# connect.net
KiCad netlist of a schematic drawn in Altium Designer
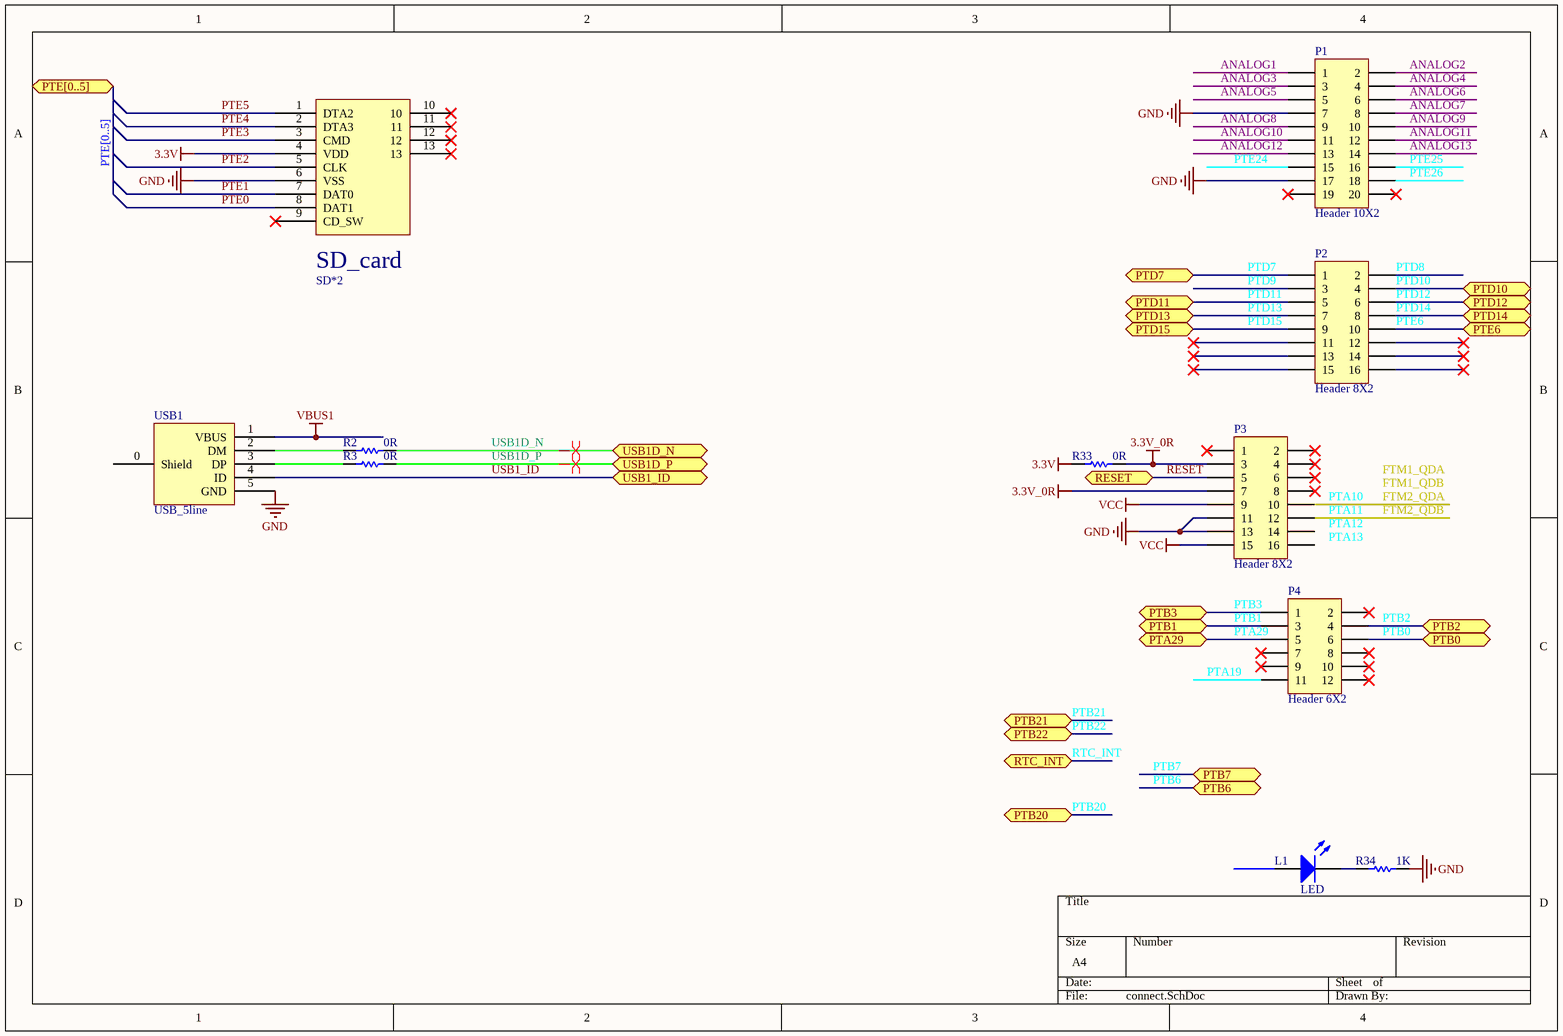
[diagram p0: connect.SchDoc]

(export (version "E")
  (design (tool "Eeschema 10.0.6"))
  (components
    (comp (ref "L1") (value "LED") (footprint "1608[0603]") (libsource (lib "Sparks") (part "LED")))
    (comp (ref "P1")
      (value "Header 10X2")
      (footprint "HDR2X10")
      (description "Header, 10-Pin, Dual row")
      (fields (field (name "PUBLISHER") "Altium Limited"))
      (libsource (lib "Sparks") (part "Header 10X2"))
    )
    (comp (ref "P2")
      (value "Header 8X2")
      (footprint "HDR2X8")
      (description "Header, 8-Pin, Dual row")
      (fields (field (name "PUBLISHER") "Altium Limited"))
      (libsource (lib "Sparks") (part "Header 8X2"))
    )
    (comp (ref "P3")
      (value "Header 8X2")
      (footprint "HDR2X8")
      (description "Header, 8-Pin, Dual row")
      (fields (field (name "PUBLISHER") "Altium Limited"))
      (libsource (lib "Sparks") (part "Header 8X2"))
    )
    (comp (ref "P4")
      (value "Header 6X2")
      (footprint "HDR2X6")
      (description "Header, 6-Pin, Dual row")
      (fields (field (name "PUBLISHER") "Altium Limited"))
      (libsource (lib "Sparks") (part "Header 6X2"))
    )
    (comp (ref "R2")
      (value "0R")
      (footprint "1608[0603]")
      (description "贴片电阻")
      (fields (field (name "Comment") "Res") (field (name "PUBLISHER") "Altium Limited"))
      (libsource (lib "Sparks") (part "Res"))
    )
    (comp (ref "R3")
      (value "0R")
      (footprint "1608[0603]")
      (description "贴片电阻")
      (fields (field (name "Comment") "Res") (field (name "PUBLISHER") "Altium Limited"))
      (libsource (lib "Sparks") (part "Res"))
    )
    (comp (ref "R33")
      (value "0R")
      (footprint "1206")
      (description "贴片电阻")
      (fields (field (name "Comment") "Res") (field (name "PUBLISHER") "Altium Limited"))
      (libsource (lib "Sparks") (part "Res"))
    )
    (comp (ref "R34")
      (value "1K")
      (footprint "1608[0603]")
      (description "贴片电阻")
      (fields (field (name "Comment") "Res") (field (name "PUBLISHER") "Altium Limited"))
      (libsource (lib "Sparks") (part "Res"))
    )
    (comp (ref "SD*2") (value "TF_card") (footprint "TF卡座(短体)") (libsource (lib "2号库") (part "TF_card")))
    (comp (ref "USB1")
      (value "USB_5line")
      (footprint "USB-MICRO-5P-2F")
      (libsource (lib "2号库") (part "USB_5line"))
    )
  )
  (nets
    (net (code "1") (name "/ANALOG1") (class "Default")
      (node (ref "P1") (pin "1") (pinfunction "1_1") (pintype "passive"))
    )
    (net (code "2") (name "/ANALOG2") (class "Default")
      (node (ref "P1") (pin "2") (pinfunction "2_2") (pintype "passive"))
    )
    (net (code "3") (name "/ANALOG3") (class "Default")
      (node (ref "P1") (pin "3") (pinfunction "3_3") (pintype "passive"))
    )
    (net (code "4") (name "/ANALOG4") (class "Default")
      (node (ref "P1") (pin "4") (pinfunction "4_4") (pintype "passive"))
    )
    (net (code "5") (name "/ANALOG5") (class "Default")
      (node (ref "P1") (pin "5") (pinfunction "5_5") (pintype "passive"))
    )
    (net (code "6") (name "/ANALOG6") (class "Default")
      (node (ref "P1") (pin "6") (pinfunction "6_6") (pintype "passive"))
    )
    (net (code "7") (name "/ANALOG7") (class "Default")
      (node (ref "P1") (pin "8") (pinfunction "8_8") (pintype "passive"))
    )
    (net (code "8") (name "/ANALOG8") (class "Default")
      (node (ref "P1") (pin "9") (pinfunction "9_9") (pintype "passive"))
    )
    (net (code "9") (name "/ANALOG9") (class "Default")
      (node (ref "P1") (pin "10") (pinfunction "10_10") (pintype "passive"))
    )
    (net (code "10") (name "/ANALOG10") (class "Default")
      (node (ref "P1") (pin "11") (pinfunction "11_11") (pintype "passive"))
    )
    (net (code "11") (name "/ANALOG11") (class "Default")
      (node (ref "P1") (pin "12") (pinfunction "12_12") (pintype "passive"))
    )
    (net (code "12") (name "/ANALOG12") (class "Default")
      (node (ref "P1") (pin "13") (pinfunction "13_13") (pintype "passive"))
    )
    (net (code "13") (name "/ANALOG13") (class "Default")
      (node (ref "P1") (pin "14") (pinfunction "14_14") (pintype "passive"))
    )
    (net (code "16") (name "/FTM2_QDA") (class "Default")
      (node (ref "P3") (pin "10") (pinfunction "10_10") (pintype "passive"))
    )
    (net (code "17") (name "/FTM2_QDB") (class "Default")
      (node (ref "P3") (pin "12") (pinfunction "12_12") (pintype "passive"))
    )
    (net (code "20") (name "/PTA19") (class "Default")
      (node (ref "P4") (pin "11") (pinfunction "11_11") (pintype "passive"))
    )
    (net (code "21") (name "/PTA29") (class "Default")
      (node (ref "P4") (pin "5") (pinfunction "5_5") (pintype "passive"))
    )
    (net (code "22") (name "/PTB0") (class "Default")
      (node (ref "P4") (pin "6") (pinfunction "6_6") (pintype "passive"))
    )
    (net (code "23") (name "/PTB1") (class "Default")
      (node (ref "P4") (pin "3") (pinfunction "3_3") (pintype "passive"))
    )
    (net (code "24") (name "/PTB2") (class "Default")
      (node (ref "P4") (pin "4") (pinfunction "4_4") (pintype "passive"))
    )
    (net (code "25") (name "/PTB3") (class "Default")
      (node (ref "P4") (pin "1") (pinfunction "1_1") (pintype "passive"))
    )
    (net (code "31") (name "/PTD7") (class "Default")
      (node (ref "P2") (pin "1") (pinfunction "1_1") (pintype "passive"))
    )
    (net (code "32") (name "/PTD8") (class "Default")
      (node (ref "P2") (pin "2") (pinfunction "2_2") (pintype "passive"))
    )
    (net (code "33") (name "/PTD9") (class "Default")
      (node (ref "P2") (pin "3") (pinfunction "3_3") (pintype "passive"))
    )
    (net (code "34") (name "/PTD10") (class "Default")
      (node (ref "P2") (pin "4") (pinfunction "4_4") (pintype "passive"))
    )
    (net (code "35") (name "/PTD11") (class "Default")
      (node (ref "P2") (pin "5") (pinfunction "5_5") (pintype "passive"))
    )
    (net (code "36") (name "/PTD12") (class "Default")
      (node (ref "P2") (pin "6") (pinfunction "6_6") (pintype "passive"))
    )
    (net (code "37") (name "/PTD13") (class "Default")
      (node (ref "P2") (pin "7") (pinfunction "7_7") (pintype "passive"))
    )
    (net (code "38") (name "/PTD14") (class "Default")
      (node (ref "P2") (pin "8") (pinfunction "8_8") (pintype "passive"))
    )
    (net (code "39") (name "/PTD15") (class "Default")
      (node (ref "P2") (pin "9") (pinfunction "9_9") (pintype "passive"))
    )
    (net (code "40") (name "/PTE0") (class "Default")
      (node (ref "SD*2") (pin "8") (pinfunction "DAT1_8") (pintype "passive"))
    )
    (net (code "41") (name "/PTE1") (class "Default")
      (node (ref "SD*2") (pin "7") (pinfunction "DAT0_7") (pintype "passive"))
    )
    (net (code "42") (name "/PTE2") (class "Default")
      (node (ref "SD*2") (pin "5") (pinfunction "CLK_5") (pintype "passive"))
    )
    (net (code "43") (name "/PTE3") (class "Default")
      (node (ref "SD*2") (pin "3") (pinfunction "CMD_3") (pintype "passive"))
    )
    (net (code "44") (name "/PTE4") (class "Default")
      (node (ref "SD*2") (pin "2") (pinfunction "DTA3_2") (pintype "passive"))
    )
    (net (code "45") (name "/PTE5") (class "Default")
      (node (ref "SD*2") (pin "1") (pinfunction "DTA2_1") (pintype "passive"))
    )
    (net (code "46") (name "/PTE6") (class "Default")
      (node (ref "P2") (pin "10") (pinfunction "10_10") (pintype "passive"))
    )
    (net (code "47") (name "/PTE24") (class "Default")
      (node (ref "P1") (pin "15") (pinfunction "15_15") (pintype "passive"))
    )
    (net (code "48") (name "/PTE25") (class "Default")
      (node (ref "P1") (pin "16") (pinfunction "16_16") (pintype "passive"))
    )
    (net (code "49") (name "/PTE26") (class "Default")
      (node (ref "P1") (pin "18") (pinfunction "18_18") (pintype "passive"))
    )
    (net (code "51") (name "/RESET") (class "Default")
      (node (ref "P3") (pin "5") (pinfunction "5_5") (pintype "passive"))
    )
    (net (code "53") (name "/USB1D_N") (class "Default")
      (node (ref "R2") (pin "1") (pinfunction "1_1") (pintype "passive"))
    )
    (net (code "54") (name "/USB1D_P") (class "Default")
      (node (ref "R3") (pin "1") (pinfunction "1_1") (pintype "passive"))
    )
    (net (code "55") (name "/USB1_ID") (class "Default")
      (node (ref "USB1") (pin "4") (pinfunction "ID_4") (pintype "passive"))
    )
    (net (code "56") (name "3.3V") (class "Default")
      (node (ref "R33") (pin "2") (pinfunction "2_2") (pintype "passive"))
      (node (ref "SD*2") (pin "4") (pinfunction "VDD_4") (pintype "passive"))
    )
    (net (code "57") (name "3.3V_0R") (class "Default")
      (node (ref "P3") (pin "3") (pinfunction "3_3") (pintype "passive"))
      (node (ref "P3") (pin "7") (pinfunction "7_7") (pintype "passive"))
      (node (ref "R33") (pin "1") (pinfunction "1_1") (pintype "passive"))
    )
    (net (code "58") (name "GND") (class "Default")
      (node (ref "P1") (pin "17") (pinfunction "17_17") (pintype "passive"))
      (node (ref "P1") (pin "7") (pinfunction "7_7") (pintype "passive"))
      (node (ref "P3") (pin "11") (pinfunction "11_11") (pintype "passive"))
      (node (ref "P3") (pin "13") (pinfunction "13_13") (pintype "passive"))
      (node (ref "R34") (pin "1") (pinfunction "1_1") (pintype "passive"))
      (node (ref "SD*2") (pin "6") (pinfunction "VSS_6") (pintype "passive"))
      (node (ref "USB1") (pin "5") (pinfunction "GND_5") (pintype "passive"))
    )
    (net (code "59") (name "Net-(L1-K)") (class "Default")
      (node (ref "L1") (pin "2") (pinfunction "K_2") (pintype "passive"))
      (node (ref "R34") (pin "2") (pinfunction "2_2") (pintype "passive"))
    )
    (net (code "60") (name "Net-(USB1-DM)") (class "Default")
      (node (ref "R2") (pin "2") (pinfunction "2_2") (pintype "passive"))
      (node (ref "USB1") (pin "2") (pinfunction "DM_2") (pintype "passive"))
    )
    (net (code "61") (name "Net-(USB1-DP)") (class "Default")
      (node (ref "R3") (pin "2") (pinfunction "2_2") (pintype "passive"))
      (node (ref "USB1") (pin "3") (pinfunction "DP_3") (pintype "passive"))
    )
    (net (code "62") (name "VBUS1") (class "Default")
      (node (ref "USB1") (pin "1") (pinfunction "VBUS_1") (pintype "passive"))
    )
    (net (code "63") (name "VCC") (class "Default")
      (node (ref "P3") (pin "15") (pinfunction "15_15") (pintype "passive"))
      (node (ref "P3") (pin "9") (pinfunction "9_9") (pintype "passive"))
    )
    (net (code "64") (name "unconnected-(L1-A-Pad1)") (class "Default")
      (node (ref "L1") (pin "1") (pinfunction "A_1") (pintype "passive"))
    )
    (net (code "65") (name "unconnected-(P1-Pad19)") (class "Default")
      (node (ref "P1") (pin "19") (pinfunction "19_19") (pintype "passive+no_connect"))
    )
    (net (code "66") (name "unconnected-(P1-Pad20)") (class "Default")
      (node (ref "P1") (pin "20") (pinfunction "20_20") (pintype "passive+no_connect"))
    )
    (net (code "67") (name "unconnected-(P2-Pad11)") (class "Default")
      (node (ref "P2") (pin "11") (pinfunction "11_11") (pintype "passive+no_connect"))
    )
    (net (code "68") (name "unconnected-(P2-Pad12)") (class "Default")
      (node (ref "P2") (pin "12") (pinfunction "12_12") (pintype "passive+no_connect"))
    )
    (net (code "69") (name "unconnected-(P2-Pad13)") (class "Default")
      (node (ref "P2") (pin "13") (pinfunction "13_13") (pintype "passive+no_connect"))
    )
    (net (code "70") (name "unconnected-(P2-Pad14)") (class "Default")
      (node (ref "P2") (pin "14") (pinfunction "14_14") (pintype "passive+no_connect"))
    )
    (net (code "71") (name "unconnected-(P2-Pad15)") (class "Default")
      (node (ref "P2") (pin "15") (pinfunction "15_15") (pintype "passive+no_connect"))
    )
    (net (code "72") (name "unconnected-(P2-Pad16)") (class "Default")
      (node (ref "P2") (pin "16") (pinfunction "16_16") (pintype "passive+no_connect"))
    )
    (net (code "73") (name "unconnected-(P3-Pad1)") (class "Default")
      (node (ref "P3") (pin "1") (pinfunction "1_1") (pintype "passive+no_connect"))
    )
    (net (code "74") (name "unconnected-(P3-Pad2)") (class "Default")
      (node (ref "P3") (pin "2") (pinfunction "2_2") (pintype "passive+no_connect"))
    )
    (net (code "75") (name "unconnected-(P3-Pad4)") (class "Default")
      (node (ref "P3") (pin "4") (pinfunction "4_4") (pintype "passive+no_connect"))
    )
    (net (code "76") (name "unconnected-(P3-Pad6)") (class "Default")
      (node (ref "P3") (pin "6") (pinfunction "6_6") (pintype "passive+no_connect"))
    )
    (net (code "77") (name "unconnected-(P3-Pad8)") (class "Default")
      (node (ref "P3") (pin "8") (pinfunction "8_8") (pintype "passive+no_connect"))
    )
    (net (code "78") (name "unconnected-(P3-Pad14)") (class "Default")
      (node (ref "P3") (pin "14") (pinfunction "14_14") (pintype "passive"))
    )
    (net (code "79") (name "unconnected-(P3-Pad16)") (class "Default")
      (node (ref "P3") (pin "16") (pinfunction "16_16") (pintype "passive"))
    )
    (net (code "80") (name "unconnected-(P4-Pad2)") (class "Default")
      (node (ref "P4") (pin "2") (pinfunction "2_2") (pintype "passive+no_connect"))
    )
    (net (code "81") (name "unconnected-(P4-Pad7)") (class "Default")
      (node (ref "P4") (pin "7") (pinfunction "7_7") (pintype "passive+no_connect"))
    )
    (net (code "82") (name "unconnected-(P4-Pad8)") (class "Default")
      (node (ref "P4") (pin "8") (pinfunction "8_8") (pintype "passive+no_connect"))
    )
    (net (code "83") (name "unconnected-(P4-Pad9)") (class "Default")
      (node (ref "P4") (pin "9") (pinfunction "9_9") (pintype "passive+no_connect"))
    )
    (net (code "84") (name "unconnected-(P4-Pad10)") (class "Default")
      (node (ref "P4") (pin "10") (pinfunction "10_10") (pintype "passive+no_connect"))
    )
    (net (code "85") (name "unconnected-(P4-Pad12)") (class "Default")
      (node (ref "P4") (pin "12") (pinfunction "12_12") (pintype "passive+no_connect"))
    )
    (net (code "86") (name "unconnected-(SD*2-CD_SW-Pad9)") (class "Default")
      (node (ref "SD*2") (pin "9") (pinfunction "CD_SW_9") (pintype "passive+no_connect"))
    )
    (net (code "87") (name "unconnected-(SD*2-Pad10)") (class "Default")
      (node (ref "SD*2") (pin "10") (pinfunction "10_10") (pintype "passive+no_connect"))
    )
    (net (code "88") (name "unconnected-(SD*2-Pad11)") (class "Default")
      (node (ref "SD*2") (pin "11") (pinfunction "11_11") (pintype "passive+no_connect"))
    )
    (net (code "89") (name "unconnected-(SD*2-Pad12)") (class "Default")
      (node (ref "SD*2") (pin "12") (pinfunction "12_12") (pintype "passive+no_connect"))
    )
    (net (code "90") (name "unconnected-(SD*2-Pad13)") (class "Default")
      (node (ref "SD*2") (pin "13") (pinfunction "13_13") (pintype "passive+no_connect"))
    )
    (net (code "91") (name "unconnected-(USB1-Shield-Pad0)") (class "Default")
      (node (ref "USB1") (pin "0") (pinfunction "Shield_0") (pintype "passive"))
    )
  )
)
